# pushbutton.net
KiCad netlist of a schematic drawn in Altium Designer
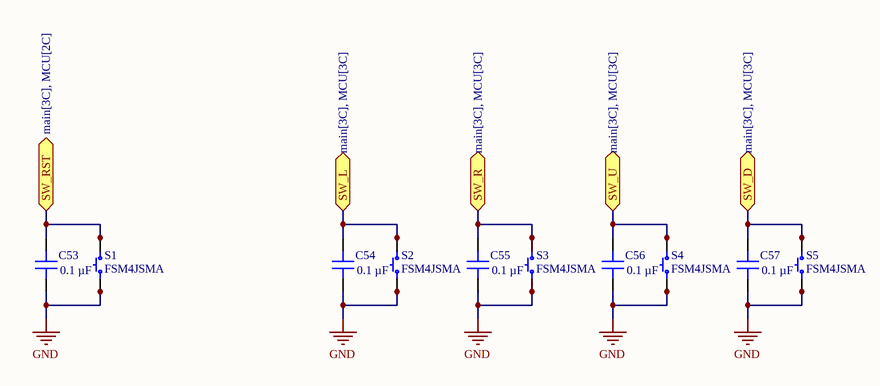
[diagram p0: pushbutton.SchDoc]

(export (version "E")
  (design (tool "Eeschema 10.0.6"))
  (components
    (comp (ref "C53")
      (value "0.1 µF")
      (footprint "CAP 1206_3216 - 0.8MM")
      (description "CAP CER 0.1UF 50V X7R 1206")
      (fields
        (field (name "PART NUMBER") "885012208087")
        (field (name "CAPACITANCE") "0.1 µF")
        (field (name "MANUFACTURER") "Würth Elektronik")
      )
      (libsource (lib "Celestial Altium Library - altium_library") (part "Capacitor"))
    )
    (comp (ref "C54")
      (value "0.1 µF")
      (footprint "CAP 1206_3216 - 0.8MM")
      (description "CAP CER 0.1UF 50V X7R 1206")
      (fields
        (field (name "PART NUMBER") "885012208087")
        (field (name "CAPACITANCE") "0.1 µF")
        (field (name "MANUFACTURER") "Würth Elektronik")
      )
      (libsource (lib "Celestial Altium Library - altium_library") (part "Capacitor"))
    )
    (comp (ref "C55")
      (value "0.1 µF")
      (footprint "CAP 1206_3216 - 0.8MM")
      (description "CAP CER 0.1UF 50V X7R 1206")
      (fields
        (field (name "PART NUMBER") "885012208087")
        (field (name "CAPACITANCE") "0.1 µF")
        (field (name "MANUFACTURER") "Würth Elektronik")
      )
      (libsource (lib "Celestial Altium Library - altium_library") (part "Capacitor"))
    )
    (comp (ref "C56")
      (value "0.1 µF")
      (footprint "CAP 1206_3216 - 0.8MM")
      (description "CAP CER 0.1UF 50V X7R 1206")
      (fields
        (field (name "PART NUMBER") "885012208087")
        (field (name "CAPACITANCE") "0.1 µF")
        (field (name "MANUFACTURER") "Würth Elektronik")
      )
      (libsource (lib "Celestial Altium Library - altium_library") (part "Capacitor"))
    )
    (comp (ref "C57")
      (value "0.1 µF")
      (footprint "CAP 1206_3216 - 0.8MM")
      (description "CAP CER 0.1UF 50V X7R 1206")
      (fields
        (field (name "PART NUMBER") "885012208087")
        (field (name "CAPACITANCE") "0.1 µF")
        (field (name "MANUFACTURER") "Würth Elektronik")
      )
      (libsource (lib "Celestial Altium Library - altium_library") (part "Capacitor"))
    )
    (comp (ref "S1")
      (value "FSM4JSMA")
      (footprint "TE FSM4JSMA")
      (description "SWITCH TACTILE SPST-NO 0.05A 24V")
      (fields (field (name "MANUFACTURER") "TE Connectivity ALCOSWITCH Switches"))
      (libsource (lib "Celestial Altium Library - altium_library") (part "SPST-NO 4 PIN"))
    )
    (comp (ref "S2")
      (value "FSM4JSMA")
      (footprint "TE FSM4JSMA")
      (description "SWITCH TACTILE SPST-NO 0.05A 24V")
      (fields (field (name "MANUFACTURER") "TE Connectivity ALCOSWITCH Switches"))
      (libsource (lib "Celestial Altium Library - altium_library") (part "SPST-NO 4 PIN"))
    )
    (comp (ref "S3")
      (value "FSM4JSMA")
      (footprint "TE FSM4JSMA")
      (description "SWITCH TACTILE SPST-NO 0.05A 24V")
      (fields (field (name "MANUFACTURER") "TE Connectivity ALCOSWITCH Switches"))
      (libsource (lib "Celestial Altium Library - altium_library") (part "SPST-NO 4 PIN"))
    )
    (comp (ref "S4")
      (value "FSM4JSMA")
      (footprint "TE FSM4JSMA")
      (description "SWITCH TACTILE SPST-NO 0.05A 24V")
      (fields (field (name "MANUFACTURER") "TE Connectivity ALCOSWITCH Switches"))
      (libsource (lib "Celestial Altium Library - altium_library") (part "SPST-NO 4 PIN"))
    )
    (comp (ref "S5")
      (value "FSM4JSMA")
      (footprint "TE FSM4JSMA")
      (description "SWITCH TACTILE SPST-NO 0.05A 24V")
      (fields (field (name "MANUFACTURER") "TE Connectivity ALCOSWITCH Switches"))
      (libsource (lib "Celestial Altium Library - altium_library") (part "SPST-NO 4 PIN"))
    )
  )
  (nets
    (net (code "1") (name "/SW_D") (class "Default")
      (node (ref "C57") (pin "2") (pinfunction "2_2") (pintype "passive"))
      (node (ref "S5") (pin "3") (pinfunction "3_3") (pintype "passive"))
      (node (ref "S5") (pin "4") (pinfunction "4_4") (pintype "passive"))
    )
    (net (code "2") (name "/SW_L") (class "Default")
      (node (ref "C54") (pin "2") (pinfunction "2_2") (pintype "passive"))
      (node (ref "S2") (pin "3") (pinfunction "3_3") (pintype "passive"))
      (node (ref "S2") (pin "4") (pinfunction "4_4") (pintype "passive"))
    )
    (net (code "3") (name "/SW_R") (class "Default")
      (node (ref "C55") (pin "2") (pinfunction "2_2") (pintype "passive"))
      (node (ref "S3") (pin "3") (pinfunction "3_3") (pintype "passive"))
      (node (ref "S3") (pin "4") (pinfunction "4_4") (pintype "passive"))
    )
    (net (code "4") (name "/SW_RST") (class "Default")
      (node (ref "C53") (pin "2") (pinfunction "2_2") (pintype "passive"))
      (node (ref "S1") (pin "3") (pinfunction "3_3") (pintype "passive"))
      (node (ref "S1") (pin "4") (pinfunction "4_4") (pintype "passive"))
    )
    (net (code "5") (name "/SW_U") (class "Default")
      (node (ref "C56") (pin "2") (pinfunction "2_2") (pintype "passive"))
      (node (ref "S4") (pin "3") (pinfunction "3_3") (pintype "passive"))
      (node (ref "S4") (pin "4") (pinfunction "4_4") (pintype "passive"))
    )
    (net (code "6") (name "GND") (class "Default")
      (node (ref "C53") (pin "1") (pinfunction "1_1") (pintype "passive"))
      (node (ref "C54") (pin "1") (pinfunction "1_1") (pintype "passive"))
      (node (ref "C55") (pin "1") (pinfunction "1_1") (pintype "passive"))
      (node (ref "C56") (pin "1") (pinfunction "1_1") (pintype "passive"))
      (node (ref "C57") (pin "1") (pinfunction "1_1") (pintype "passive"))
      (node (ref "S1") (pin "1") (pinfunction "1_1") (pintype "passive"))
      (node (ref "S1") (pin "2") (pinfunction "2_2") (pintype "passive"))
      (node (ref "S2") (pin "1") (pinfunction "1_1") (pintype "passive"))
      (node (ref "S2") (pin "2") (pinfunction "2_2") (pintype "passive"))
      (node (ref "S3") (pin "1") (pinfunction "1_1") (pintype "passive"))
      (node (ref "S3") (pin "2") (pinfunction "2_2") (pintype "passive"))
      (node (ref "S4") (pin "1") (pinfunction "1_1") (pintype "passive"))
      (node (ref "S4") (pin "2") (pinfunction "2_2") (pintype "passive"))
      (node (ref "S5") (pin "1") (pinfunction "1_1") (pintype "passive"))
      (node (ref "S5") (pin "2") (pinfunction "2_2") (pintype "passive"))
    )
  )
)
